# L6470_AutoDriver.net
KiCad netlist of a schematic drawn in EAGLE
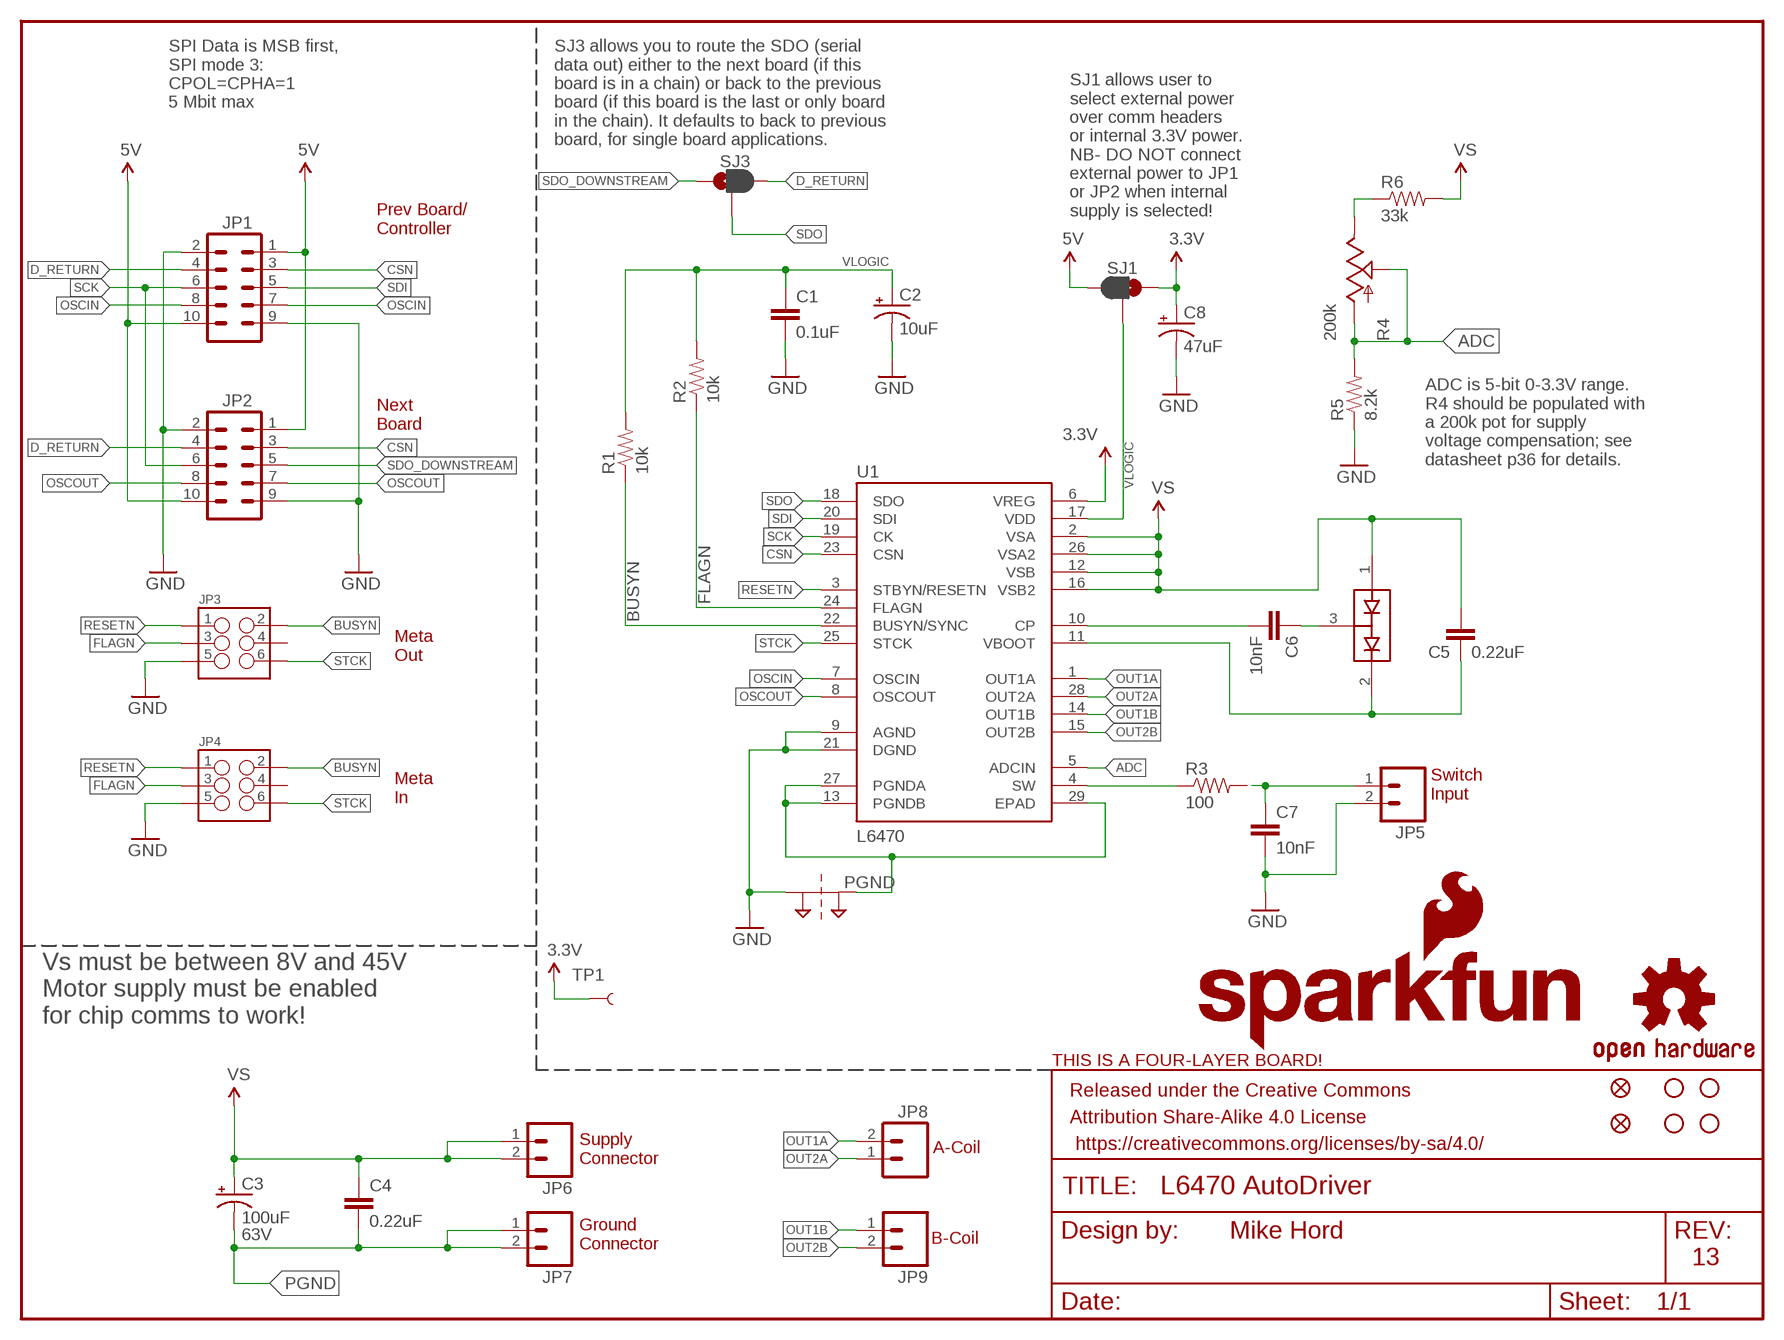
[diagram p0: schematic, sheet 1]

(export (version "E")
  (design (tool "Eeschema 10.0.6"))
  (components
    (comp (ref "C1")
      (value "0.1uF")
      (footprint "eagle-import:0603-CAP")
      (libsource (lib "eagle-import") (part "0.1UF-25V(+80/-20%)(0603)"))
    )
    (comp (ref "C2")
      (value "10uF")
      (footprint "eagle-import:EIA3216")
      (libsource (lib "eagle-import") (part "10UF-TANT"))
    )
    (comp (ref "C3")
      (value "100uF")
      (footprint "eagle-import:NIC_10X10.5_CAP")
      (libsource (lib "eagle-import") (part "100UF-63V-20%(ELECT)"))
    )
    (comp (ref "C4")
      (value "0.22uF")
      (footprint "eagle-import:0603-CAP")
      (libsource (lib "eagle-import") (part "0.22UF50V-20%,+80%(0603)"))
    )
    (comp (ref "C5")
      (value "0.22uF")
      (footprint "eagle-import:0603-CAP")
      (libsource (lib "eagle-import") (part "0.22UF50V-20%,+80%(0603)"))
    )
    (comp (ref "C6")
      (value "10nF")
      (footprint "eagle-import:0603-CAP")
      (libsource (lib "eagle-import") (part "10NF/10000PF-50V-10%(0603)"))
    )
    (comp (ref "C7")
      (value "10nF")
      (footprint "eagle-import:0603-CAP")
      (libsource (lib "eagle-import") (part "10NF/10000PF-50V-10%(0603)"))
    )
    (comp (ref "C8")
      (value "47uF")
      (footprint "eagle-import:EIA3528")
      (libsource (lib "eagle-import") (part "47UF-TANT"))
    )
    (comp (ref "D1")
      (value "BAV99")
      (footprint "eagle-import:SOT23-3")
      (libsource (lib "eagle-import") (part "BAV99"))
    )
    (comp (ref "FID1")
      (value "FIDUCIALUFIDUCIAL")
      (footprint "eagle-import:MICRO-FIDUCIAL")
      (libsource (lib "eagle-import") (part "FIDUCIALUFIDUCIAL"))
    )
    (comp (ref "FID2")
      (value "FIDUCIALUFIDUCIAL")
      (footprint "eagle-import:MICRO-FIDUCIAL")
      (libsource (lib "eagle-import") (part "FIDUCIALUFIDUCIAL"))
    )
    (comp (ref "FRAME1")
      (value "FRAME-LETTER")
      (footprint "eagle-import:CREATIVE_COMMONS")
      (libsource (lib "eagle-import") (part "FRAME-LETTER"))
    )
    (comp (ref "JP1")
      (value "M05X2SHD")
      (footprint "eagle-import:2X5-SHROUDED")
      (libsource (lib "eagle-import") (part "M05X2SHD"))
    )
    (comp (ref "JP2")
      (value "M05X2SHD")
      (footprint "eagle-import:2X5-SHROUDED")
      (libsource (lib "eagle-import") (part "M05X2SHD"))
    )
    (comp (ref "JP3")
      (value "M03X2SHROUD")
      (footprint "eagle-import:2X3-SHROUDED")
      (libsource (lib "eagle-import") (part "M03X2SHROUD"))
    )
    (comp (ref "JP4")
      (value "M03X2SHROUD")
      (footprint "eagle-import:2X3-SHROUDED")
      (libsource (lib "eagle-import") (part "M03X2SHROUD"))
    )
    (comp (ref "JP5")
      (value "M023.5MM")
      (footprint "eagle-import:SCREWTERMINAL-3.5MM-2")
      (libsource (lib "eagle-import") (part "M023.5MM"))
    )
    (comp (ref "JP6")
      (value "M023.5MM")
      (footprint "eagle-import:SCREWTERMINAL-3.5MM-2")
      (libsource (lib "eagle-import") (part "M023.5MM"))
    )
    (comp (ref "JP7")
      (value "M023.5MM")
      (footprint "eagle-import:SCREWTERMINAL-3.5MM-2")
      (libsource (lib "eagle-import") (part "M023.5MM"))
    )
    (comp (ref "JP8")
      (value "M023.5MM")
      (footprint "eagle-import:SCREWTERMINAL-3.5MM-2")
      (libsource (lib "eagle-import") (part "M023.5MM"))
    )
    (comp (ref "JP9")
      (value "M023.5MM")
      (footprint "eagle-import:SCREWTERMINAL-3.5MM-2")
      (libsource (lib "eagle-import") (part "M023.5MM"))
    )
    (comp (ref "LOGO1")
      (value "OSHW-LOGOM")
      (footprint "eagle-import:OSHW-LOGO-M")
      (libsource (lib "eagle-import") (part "OSHW-LOGOM"))
    )
    (comp (ref "LOGO2")
      (value "SFE_LOGO_NAME_FLAME.2_INCH")
      (footprint "eagle-import:SFE_LOGO_NAME_FLAME_.2")
      (libsource (lib "eagle-import") (part "SFE_LOGO_NAME_FLAME.2_INCH"))
    )
    (comp (ref "R1")
      (value "10k")
      (footprint "eagle-import:0603-RES")
      (libsource (lib "eagle-import") (part "10KOHM1/10W1%(0603)0603"))
    )
    (comp (ref "R2")
      (value "10k")
      (footprint "eagle-import:0603-RES")
      (libsource (lib "eagle-import") (part "10KOHM1/10W1%(0603)0603"))
    )
    (comp (ref "R3")
      (value "100")
      (footprint "eagle-import:0603-RES")
      (libsource (lib "eagle-import") (part "100OHM1/10W1%(0603)"))
    )
    (comp (ref "R4")
      (value "200k")
      (footprint "eagle-import:3362U")
      (libsource (lib "eagle-import") (part "POT100K_3362U"))
    )
    (comp (ref "R5")
      (value "8.2k")
      (footprint "eagle-import:0603-RES")
      (libsource (lib "eagle-import") (part "8.2KOHM-1/10W-5%(0603)"))
    )
    (comp (ref "R6")
      (value "33k")
      (footprint "eagle-import:0603-RES")
      (libsource (lib "eagle-import") (part "33KOHM1/10W1%(0603)"))
    )
    (comp (ref "SJ1")
      (value "JUMPER-PAD-3-2OF3_NC_BY_PASTE")
      (footprint "eagle-import:PAD-JUMPER-3-2OF3_NC_BY_PASTE_YES_SILK_FULL_BOX")
      (libsource (lib "eagle-import") (part "JUMPER-PAD-3-2OF3_NC_BY_PASTE"))
    )
    (comp (ref "SJ2")
      (value "2PT_GND_TIE")
      (footprint "eagle-import:2PT_GND_TIE")
      (libsource (lib "eagle-import") (part "2PT_GND_TIE"))
    )
    (comp (ref "SJ3")
      (value "JUMPER-PAD-3-2OF3_NC_BY_PASTE")
      (footprint "eagle-import:PAD-JUMPER-3-2OF3_NC_BY_PASTE_YES_SILK_FULL_BOX")
      (libsource (lib "eagle-import") (part "JUMPER-PAD-3-2OF3_NC_BY_PASTE"))
    )
    (comp (ref "STANDOFF1")
      (value "STAND-OFF")
      (footprint "eagle-import:STAND-OFF")
      (libsource (lib "eagle-import") (part "STAND-OFF"))
    )
    (comp (ref "STANDOFF2")
      (value "STAND-OFF")
      (footprint "eagle-import:STAND-OFF")
      (libsource (lib "eagle-import") (part "STAND-OFF"))
    )
    (comp (ref "STANDOFF3")
      (value "STAND-OFF")
      (footprint "eagle-import:STAND-OFF")
      (libsource (lib "eagle-import") (part "STAND-OFF"))
    )
    (comp (ref "STANDOFF4")
      (value "STAND-OFF")
      (footprint "eagle-import:STAND-OFF")
      (libsource (lib "eagle-import") (part "STAND-OFF"))
    )
    (comp (ref "TP1")
      (value "TEST-POINTTP_15TH_THRU")
      (footprint "eagle-import:TP_15TH")
      (libsource (lib "eagle-import") (part "TEST-POINTTP_15TH_THRU"))
    )
    (comp (ref "U$4")
      (value "FOUR_LAYER_WARNING")
      (footprint "eagle-import:FOUR_LAYER_WARNING")
      (libsource (lib "eagle-import") (part "FOUR_LAYER_WARNING"))
    )
    (comp (ref "U1")
      (value "L6470")
      (footprint "eagle-import:HTSSOP28")
      (libsource (lib "eagle-import") (part "L6470"))
    )
  )
  (nets
    (net (code "1") (name "/VLOGIC") (class "Default")
      (node (ref "C1") (pin "1") (pinfunction "1_1") (pintype "passive"))
      (node (ref "C2") (pin "A") (pinfunction "+_A") (pintype "passive"))
      (node (ref "R1") (pin "2") (pinfunction "2_2") (pintype "passive"))
      (node (ref "R2") (pin "2") (pinfunction "2_2") (pintype "passive"))
      (node (ref "SJ1") (pin "2") (pinfunction "2_2") (pintype "passive"))
      (node (ref "U1") (pin "17") (pinfunction "VDD_17") (pintype "bidirectional"))
    )
    (net (code "2") (name "3.3V") (class "Default")
      (node (ref "C8") (pin "A") (pinfunction "+_A") (pintype "passive"))
      (node (ref "SJ1") (pin "1") (pinfunction "1_1") (pintype "passive"))
      (node (ref "TP1") (pin "P$1") (pinfunction "1_P$1") (pintype "bidirectional"))
      (node (ref "U1") (pin "6") (pinfunction "VREG_6") (pintype "bidirectional"))
    )
    (net (code "3") (name "5V") (class "Default")
      (node (ref "JP1") (pin "1") (pinfunction "1_1") (pintype "passive"))
      (node (ref "JP1") (pin "10") (pinfunction "10_10") (pintype "passive"))
      (node (ref "JP2") (pin "1") (pinfunction "1_1") (pintype "passive"))
      (node (ref "JP2") (pin "10") (pinfunction "10_10") (pintype "passive"))
      (node (ref "SJ1") (pin "3") (pinfunction "3_3") (pintype "passive"))
    )
    (net (code "4") (name "ADC") (class "Default")
      (node (ref "R4") (pin "P$2") (pinfunction "S_P$2") (pintype "passive"))
      (node (ref "R4") (pin "P$3") (pinfunction "A_P$3") (pintype "passive"))
      (node (ref "R5") (pin "2") (pinfunction "2_2") (pintype "passive"))
      (node (ref "U1") (pin "5") (pinfunction "ADCIN_5") (pintype "bidirectional"))
    )
    (net (code "5") (name "BUSYN") (class "Default")
      (node (ref "JP3") (pin "2") (pinfunction "2_2") (pintype "bidirectional"))
      (node (ref "JP4") (pin "2") (pinfunction "2_2") (pintype "bidirectional"))
      (node (ref "R1") (pin "1") (pinfunction "1_1") (pintype "passive"))
      (node (ref "U1") (pin "22") (pinfunction "BUSYN/SYNC_22") (pintype "bidirectional"))
    )
    (net (code "6") (name "CSN") (class "Default")
      (node (ref "JP1") (pin "3") (pinfunction "3_3") (pintype "passive"))
      (node (ref "JP2") (pin "3") (pinfunction "3_3") (pintype "passive"))
      (node (ref "U1") (pin "23") (pinfunction "CSN_23") (pintype "bidirectional"))
    )
    (net (code "7") (name "D_RETURN") (class "Default")
      (node (ref "JP1") (pin "4") (pinfunction "4_4") (pintype "passive"))
      (node (ref "JP2") (pin "4") (pinfunction "4_4") (pintype "passive"))
      (node (ref "SJ3") (pin "3") (pinfunction "3_3") (pintype "passive"))
    )
    (net (code "8") (name "FLAGN") (class "Default")
      (node (ref "JP3") (pin "3") (pinfunction "3_3") (pintype "bidirectional"))
      (node (ref "JP4") (pin "3") (pinfunction "3_3") (pintype "bidirectional"))
      (node (ref "R2") (pin "1") (pinfunction "1_1") (pintype "passive"))
      (node (ref "U1") (pin "24") (pinfunction "FLAGN_24") (pintype "bidirectional"))
    )
    (net (code "9") (name "GND") (class "Default")
      (node (ref "C1") (pin "2") (pinfunction "2_2") (pintype "passive"))
      (node (ref "C2") (pin "C") (pinfunction "-_C") (pintype "passive"))
      (node (ref "C7") (pin "2") (pinfunction "2_2") (pintype "passive"))
      (node (ref "C8") (pin "C") (pinfunction "-_C") (pintype "passive"))
      (node (ref "JP1") (pin "2") (pinfunction "2_2") (pintype "passive"))
      (node (ref "JP1") (pin "9") (pinfunction "9_9") (pintype "passive"))
      (node (ref "JP2") (pin "2") (pinfunction "2_2") (pintype "passive"))
      (node (ref "JP2") (pin "9") (pinfunction "9_9") (pintype "passive"))
      (node (ref "JP3") (pin "5") (pinfunction "5_5") (pintype "bidirectional"))
      (node (ref "JP4") (pin "5") (pinfunction "5_5") (pintype "bidirectional"))
      (node (ref "JP5") (pin "2") (pinfunction "2_2") (pintype "passive"))
      (node (ref "R5") (pin "1") (pinfunction "1_1") (pintype "passive"))
      (node (ref "SJ2") (pin "P$1") (pinfunction "P$1_P$1") (pintype "bidirectional"))
      (node (ref "U1") (pin "21") (pinfunction "DGND_21") (pintype "bidirectional"))
      (node (ref "U1") (pin "9") (pinfunction "AGND_9") (pintype "bidirectional"))
    )
    (net (code "10") (name "Net-(C7-Pad1)") (class "Default")
      (node (ref "C7") (pin "1") (pinfunction "1_1") (pintype "passive"))
      (node (ref "JP5") (pin "1") (pinfunction "1_1") (pintype "passive"))
      (node (ref "R3") (pin "2") (pinfunction "2_2") (pintype "passive"))
    )
    (net (code "11") (name "Net-(D1-C2)") (class "Default")
      (node (ref "C5") (pin "1") (pinfunction "1_1") (pintype "passive"))
      (node (ref "D1") (pin "2") (pinfunction "C2_2") (pintype "bidirectional"))
      (node (ref "U1") (pin "11") (pinfunction "VBOOT_11") (pintype "bidirectional"))
    )
    (net (code "12") (name "Net-(D1-COM)") (class "Default")
      (node (ref "C6") (pin "1") (pinfunction "1_1") (pintype "passive"))
      (node (ref "D1") (pin "3") (pinfunction "COM_3") (pintype "bidirectional"))
    )
    (net (code "13") (name "Net-(R4-E)") (class "Default")
      (node (ref "R4") (pin "P$1") (pinfunction "E_P$1") (pintype "passive"))
      (node (ref "R6") (pin "1") (pinfunction "1_1") (pintype "passive"))
    )
    (net (code "14") (name "Net-(U1-CP)") (class "Default")
      (node (ref "C6") (pin "2") (pinfunction "2_2") (pintype "passive"))
      (node (ref "U1") (pin "10") (pinfunction "CP_10") (pintype "bidirectional"))
    )
    (net (code "15") (name "Net-(U1-SW)") (class "Default")
      (node (ref "R3") (pin "1") (pinfunction "1_1") (pintype "passive"))
      (node (ref "U1") (pin "4") (pinfunction "SW_4") (pintype "bidirectional"))
    )
    (net (code "16") (name "OSCIN") (class "Default")
      (node (ref "JP1") (pin "7") (pinfunction "7_7") (pintype "passive"))
      (node (ref "JP1") (pin "8") (pinfunction "8_8") (pintype "passive"))
      (node (ref "U1") (pin "7") (pinfunction "OSCIN_7") (pintype "bidirectional"))
    )
    (net (code "17") (name "OSCOUT") (class "Default")
      (node (ref "JP2") (pin "7") (pinfunction "7_7") (pintype "passive"))
      (node (ref "JP2") (pin "8") (pinfunction "8_8") (pintype "passive"))
      (node (ref "U1") (pin "8") (pinfunction "OSCOUT_8") (pintype "bidirectional"))
    )
    (net (code "18") (name "OUT1A") (class "Default")
      (node (ref "JP8") (pin "2") (pinfunction "2_2") (pintype "passive"))
      (node (ref "U1") (pin "1") (pinfunction "OUT1A_1") (pintype "bidirectional"))
    )
    (net (code "19") (name "OUT1B") (class "Default")
      (node (ref "JP9") (pin "1") (pinfunction "1_1") (pintype "passive"))
      (node (ref "U1") (pin "14") (pinfunction "OUT1B_14") (pintype "bidirectional"))
    )
    (net (code "20") (name "OUT2A") (class "Default")
      (node (ref "JP8") (pin "1") (pinfunction "1_1") (pintype "passive"))
      (node (ref "U1") (pin "28") (pinfunction "OUT2A_28") (pintype "bidirectional"))
    )
    (net (code "21") (name "OUT2B") (class "Default")
      (node (ref "JP9") (pin "2") (pinfunction "2_2") (pintype "passive"))
      (node (ref "U1") (pin "15") (pinfunction "OUT2B_15") (pintype "bidirectional"))
    )
    (net (code "22") (name "PGND") (class "Default")
      (node (ref "C3") (pin "-") (pinfunction "-_-") (pintype "passive"))
      (node (ref "C4") (pin "2") (pinfunction "2_2") (pintype "passive"))
      (node (ref "JP7") (pin "1") (pinfunction "1_1") (pintype "passive"))
      (node (ref "JP7") (pin "2") (pinfunction "2_2") (pintype "passive"))
      (node (ref "SJ2") (pin "P$2") (pinfunction "P$2_P$2") (pintype "bidirectional"))
      (node (ref "U1") (pin "13") (pinfunction "PGNDB_13") (pintype "bidirectional"))
      (node (ref "U1") (pin "27") (pinfunction "PGNDA_27") (pintype "bidirectional"))
      (node (ref "U1") (pin "29") (pinfunction "EPAD_29") (pintype "bidirectional"))
    )
    (net (code "23") (name "RESETN") (class "Default")
      (node (ref "JP3") (pin "1") (pinfunction "1_1") (pintype "bidirectional"))
      (node (ref "JP4") (pin "1") (pinfunction "1_1") (pintype "bidirectional"))
      (node (ref "U1") (pin "3") (pinfunction "STBYN/RESETN_3") (pintype "bidirectional"))
    )
    (net (code "24") (name "SCK") (class "Default")
      (node (ref "JP1") (pin "6") (pinfunction "6_6") (pintype "passive"))
      (node (ref "JP2") (pin "6") (pinfunction "6_6") (pintype "passive"))
      (node (ref "U1") (pin "19") (pinfunction "CK_19") (pintype "bidirectional"))
    )
    (net (code "25") (name "SDI") (class "Default")
      (node (ref "JP1") (pin "5") (pinfunction "5_5") (pintype "passive"))
      (node (ref "U1") (pin "20") (pinfunction "SDI_20") (pintype "bidirectional"))
    )
    (net (code "26") (name "SDO") (class "Default")
      (node (ref "SJ3") (pin "2") (pinfunction "2_2") (pintype "passive"))
      (node (ref "U1") (pin "18") (pinfunction "SDO_18") (pintype "bidirectional"))
    )
    (net (code "27") (name "SDO_DOWNSTREAM") (class "Default")
      (node (ref "JP2") (pin "5") (pinfunction "5_5") (pintype "passive"))
      (node (ref "SJ3") (pin "1") (pinfunction "1_1") (pintype "passive"))
    )
    (net (code "28") (name "STCK") (class "Default")
      (node (ref "JP3") (pin "6") (pinfunction "6_6") (pintype "bidirectional"))
      (node (ref "JP4") (pin "6") (pinfunction "6_6") (pintype "bidirectional"))
      (node (ref "U1") (pin "25") (pinfunction "STCK_25") (pintype "bidirectional"))
    )
    (net (code "29") (name "VS") (class "Default")
      (node (ref "C3") (pin "+") (pinfunction "+_+") (pintype "passive"))
      (node (ref "C4") (pin "1") (pinfunction "1_1") (pintype "passive"))
      (node (ref "C5") (pin "2") (pinfunction "2_2") (pintype "passive"))
      (node (ref "D1") (pin "1") (pinfunction "A1_1") (pintype "bidirectional"))
      (node (ref "JP6") (pin "1") (pinfunction "1_1") (pintype "passive"))
      (node (ref "JP6") (pin "2") (pinfunction "2_2") (pintype "passive"))
      (node (ref "R6") (pin "2") (pinfunction "2_2") (pintype "passive"))
      (node (ref "U1") (pin "12") (pinfunction "VSB_12") (pintype "bidirectional"))
      (node (ref "U1") (pin "16") (pinfunction "VSB2_16") (pintype "bidirectional"))
      (node (ref "U1") (pin "2") (pinfunction "VSA_2") (pintype "bidirectional"))
      (node (ref "U1") (pin "26") (pinfunction "VSA2_26") (pintype "bidirectional"))
    )
    (net (code "30") (name "unconnected-(JP3-Pad4)") (class "Default")
      (node (ref "JP3") (pin "4") (pinfunction "4_4") (pintype "bidirectional"))
    )
    (net (code "31") (name "unconnected-(JP4-Pad4)") (class "Default")
      (node (ref "JP4") (pin "4") (pinfunction "4_4") (pintype "bidirectional"))
    )
  )
)
